# 5R_Supply.net
KiCad netlist of a schematic drawn in Altium Designer
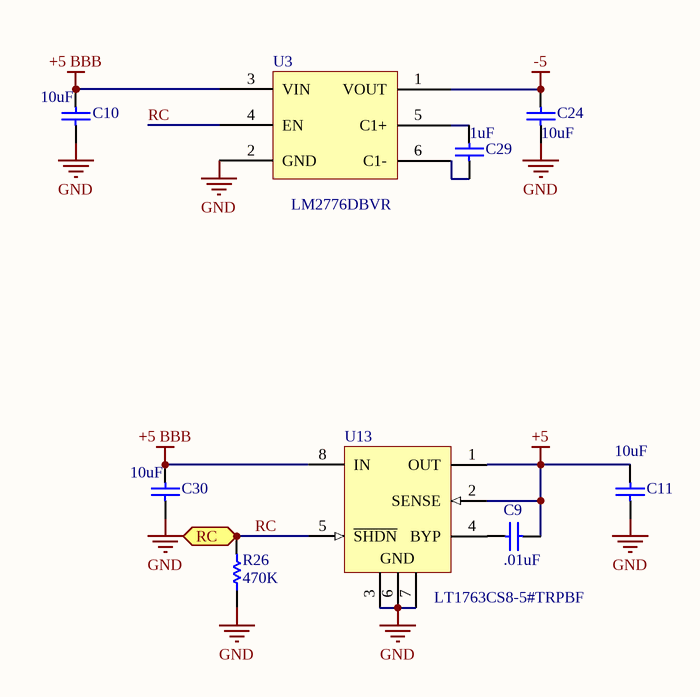
[diagram p0: 5R_Supply.SchDoc]

(export (version "E")
  (design (tool "Eeschema 10.0.6"))
  (components
    (comp (ref "C9")
      (value ".01uF")
      (footprint "CAPC0805(2012)145_N")
      (description "CAP CER 10000PF 16V X7R 0805")
      (fields
        (field (name "MANUFACTURER") "Yageo")
        (field (name "MANUFACTURER PART NUMBER") "AC0805KRX7R7BB103")
      )
      (libsource (lib "Altium Content Vault") (part "CMP-1036-04795-1"))
    )
    (comp (ref "C10")
      (value "10uF")
      (footprint "CAPC0805(2012)145_N")
      (description "CAP CER 10UF 25V X7R 0805")
      (fields
        (field (name "MANUFACTURER") "Yageo")
        (field (name "MANUFACTURER PART NUMBER") "CC0805KKX7R6BB106")
      )
      (libsource (lib "Altium Content Vault") (part "CMP-1036-04795-1"))
    )
    (comp (ref "C11")
      (value "10uF")
      (footprint "CAPC0805(2012)145_N")
      (description "CAP CER 10UF 25V X7R 0805")
      (fields
        (field (name "MANUFACTURER") "Yageo")
        (field (name "MANUFACTURER PART NUMBER") "CC0805KKX7R6BB106")
      )
      (libsource (lib "Altium Content Vault") (part "CMP-1036-04795-1"))
    )
    (comp (ref "C24")
      (value "10uF")
      (footprint "CAPC0805(2012)145_N")
      (description "CAP CER 10UF 25V X7R 0805")
      (fields
        (field (name "MANUFACTURER") "Yageo")
        (field (name "MANUFACTURER PART NUMBER") "CC0805KKX7R6BB106")
      )
      (libsource (lib "Altium Content Vault") (part "CMP-1036-04795-1"))
    )
    (comp (ref "C29")
      (value "1uF")
      (footprint "CAPC0805(2012)145_N")
      (description "CAP CER 1UF 25V X7R 0805")
      (fields
        (field (name "MANUFACTURER") "Yageo")
        (field (name "MANUFACTURER PART NUMBER") "CC0805KKX7R6BB105")
      )
      (libsource (lib "Altium Content Vault") (part "CMP-1036-04795-1"))
    )
    (comp (ref "C30")
      (value "10uF")
      (footprint "CAPC0805(2012)145_N")
      (description "CAP CER 10UF 25V X7R 0805")
      (fields
        (field (name "MANUFACTURER") "Yageo")
        (field (name "MANUFACTURER PART NUMBER") "CC0805KKX7R6BB106")
      )
      (libsource (lib "Altium Content Vault") (part "CMP-1036-04795-1"))
    )
    (comp (ref "R26")
      (value "470K")
      (footprint "RESC0805(2012)_M")
      (description "RES SMD 59K OHM 1% 1/8W 0805")
      (libsource (lib "Altium Content Vault") (part "CMP-1013-00017-1"))
    )
    (comp (ref "U3")
      (value "LM2776DBVR")
      (footprint "LM2776DBVR")
      (description "IC REG SWTCHD CAP INV 6SOT23")
      (fields (field (name "MANUFACTURER") "Texas Instruments"))
      (libsource (lib "ZLS_Schematic_lib") (part "LM2776DBVR"))
    )
    (comp (ref "U13")
      (value "LT1763CS8-5#TRPBF")
      (footprint "LT-S8-8_L")
      (description "IC REG LINEAR 5V 500MA 8SOIC")
      (fields
        (field (name "MANUFACTURER") "Linear Technology/Analog Devices")
        (field (name "BASE PART NUMBER") "LT1763")
      )
      (libsource (lib "Altium Content Vault") (part "CMP-0476-01685-1"))
    )
  )
  (nets
    (net (code "1") (name "+5") (class "Default")
      (node (ref "C11") (pin "1") (pinfunction "1_1") (pintype "passive"))
      (node (ref "C9") (pin "2") (pinfunction "2_2") (pintype "passive"))
      (node (ref "U13") (pin "1") (pinfunction "OUT_1") (pintype "power_in"))
      (node (ref "U13") (pin "2") (pinfunction "SENSE_2") (pintype "input"))
    )
    (net (code "2") (name "+5 BBB") (class "Default")
      (node (ref "C10") (pin "1") (pinfunction "1_1") (pintype "passive"))
      (node (ref "C30") (pin "1") (pinfunction "1_1") (pintype "passive"))
      (node (ref "U13") (pin "8") (pinfunction "IN_8") (pintype "power_in"))
      (node (ref "U3") (pin "3") (pinfunction "VIN_3") (pintype "passive"))
    )
    (net (code "3") (name "-5") (class "Default")
      (node (ref "C24") (pin "1") (pinfunction "1_1") (pintype "passive"))
      (node (ref "U3") (pin "1") (pinfunction "VOUT_1") (pintype "passive"))
    )
    (net (code "4") (name "/RC") (class "Default")
      (node (ref "R26") (pin "2") (pinfunction "2_2") (pintype "passive"))
      (node (ref "U13") (pin "5") (pinfunction "~{SHDN}_5") (pintype "input"))
      (node (ref "U3") (pin "4") (pinfunction "EN_4") (pintype "passive"))
    )
    (net (code "5") (name "GND") (class "Default")
      (node (ref "C10") (pin "2") (pinfunction "2_2") (pintype "passive"))
      (node (ref "C11") (pin "2") (pinfunction "2_2") (pintype "passive"))
      (node (ref "C24") (pin "2") (pinfunction "2_2") (pintype "passive"))
      (node (ref "C30") (pin "2") (pinfunction "2_2") (pintype "passive"))
      (node (ref "R26") (pin "1") (pinfunction "1_1") (pintype "passive"))
      (node (ref "U13") (pin "3") (pinfunction "GND_3") (pintype "power_in"))
      (node (ref "U13") (pin "6") (pinfunction "GND_6") (pintype "power_in"))
      (node (ref "U13") (pin "7") (pinfunction "GND_7") (pintype "power_in"))
      (node (ref "U3") (pin "2") (pinfunction "GND_2") (pintype "passive"))
    )
    (net (code "6") (name "Net-(U3-C1+)") (class "Default")
      (node (ref "C29") (pin "1") (pinfunction "1_1") (pintype "passive"))
      (node (ref "U3") (pin "5") (pinfunction "C1+_5") (pintype "passive"))
    )
    (net (code "7") (name "Net-(U3-C1-)") (class "Default")
      (node (ref "C29") (pin "2") (pinfunction "2_2") (pintype "passive"))
      (node (ref "U3") (pin "6") (pinfunction "C1-_6") (pintype "passive"))
    )
    (net (code "8") (name "Net-(U13-BYP)") (class "Default")
      (node (ref "C9") (pin "1") (pinfunction "1_1") (pintype "passive"))
      (node (ref "U13") (pin "4") (pinfunction "BYP_4") (pintype "passive"))
    )
  )
)
